# f7_General.net
KiCad netlist of a schematic drawn in EAGLE
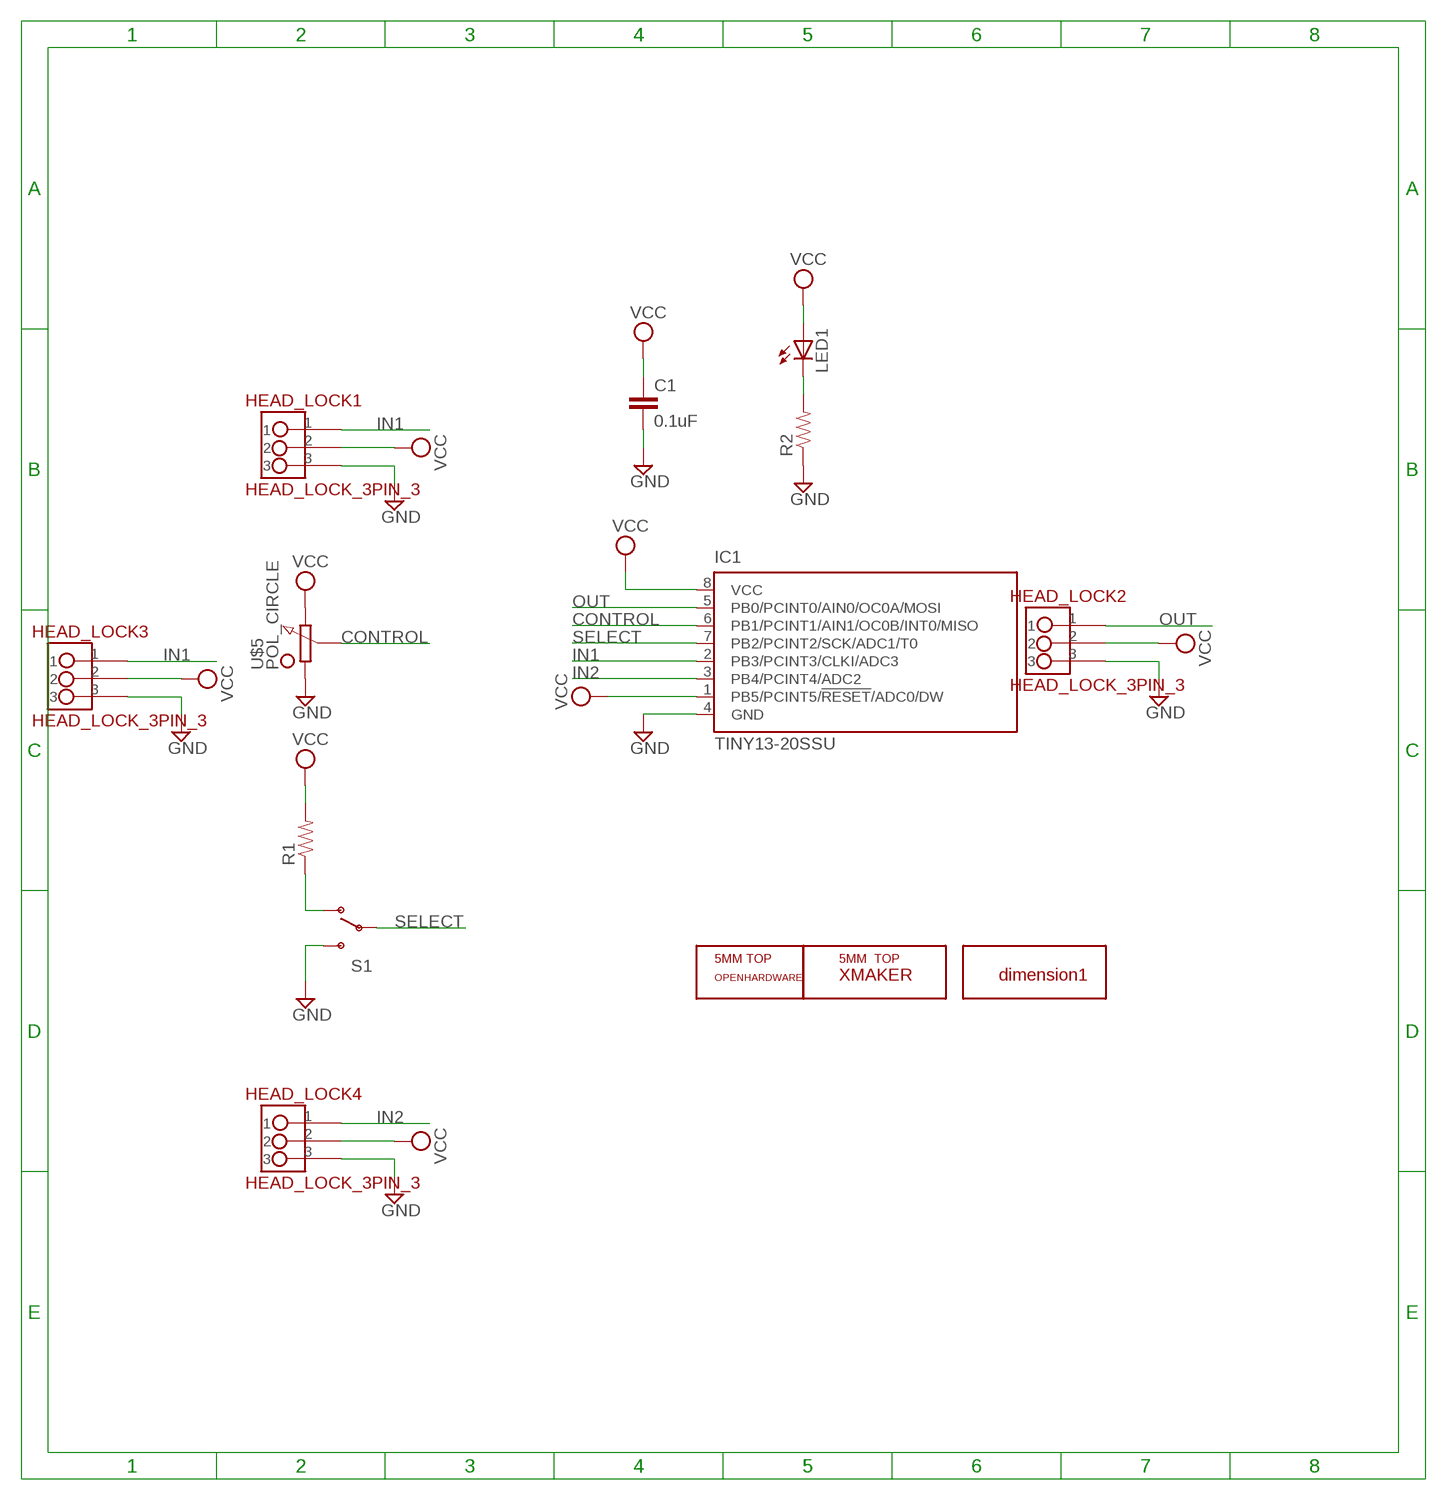
[diagram p0: schematic, sheet 1]

(export (version "E")
  (design (tool "Eeschema 10.0.6"))
  (components
    (comp (ref "C1")
      (value "0.1uF")
      (footprint "eagle-import:0603-CAP")
      (libsource (lib "eagle-import") (part "CAP0603-CAP"))
    )
    (comp (ref "HEAD_LOCK1")
      (value "HEAD_LOCK_3PIN_3")
      (footprint "eagle-import:HEAD_LOCK_3PIN_3")
      (libsource (lib "eagle-import") (part "HEAD_LOCK_3PIN_3"))
    )
    (comp (ref "HEAD_LOCK2")
      (value "HEAD_LOCK_3PIN_3")
      (footprint "eagle-import:HEAD_LOCK_3PIN_3")
      (libsource (lib "eagle-import") (part "HEAD_LOCK_3PIN_3"))
    )
    (comp (ref "HEAD_LOCK3")
      (value "HEAD_LOCK_3PIN_3")
      (footprint "eagle-import:HEAD_LOCK_3PIN_3")
      (libsource (lib "eagle-import") (part "HEAD_LOCK_3PIN_3"))
    )
    (comp (ref "HEAD_LOCK4")
      (value "HEAD_LOCK_3PIN_3")
      (footprint "eagle-import:HEAD_LOCK_3PIN_3")
      (libsource (lib "eagle-import") (part "HEAD_LOCK_3PIN_3"))
    )
    (comp (ref "IC1")
      (value "TINY13-20SSU")
      (footprint "eagle-import:8S1")
      (fields (field (name "MPN") "ATTINY13-20SSU"))
      (libsource (lib "eagle-import") (part "TINY13SSU-20"))
    )
    (comp (ref "LED1")
      (value "LED_ESML0603")
      (footprint "eagle-import:LED_SML0603")
      (libsource (lib "eagle-import") (part "LED_ESML0603"))
    )
    (comp (ref "R1")
      (value "RESISTOR0603-RES")
      (footprint "eagle-import:0603-RES")
      (libsource (lib "eagle-import") (part "RESISTOR0603-RES"))
    )
    (comp (ref "R2")
      (value "0.27OHM-1/10W-1%(0603)")
      (footprint "eagle-import:0603-RES")
      (libsource (lib "eagle-import") (part "0.27OHM-1/10W-1%(0603)"))
    )
    (comp (ref "S1")
      (value "SWITCH-SPDTKIT")
      (footprint "eagle-import:SWITCH-SPDT_KIT")
      (libsource (lib "eagle-import") (part "SWITCH-SPDTKIT"))
    )
    (comp (ref "U$2")
      (value "XMAKERLOGO_5MM_TOP")
      (footprint "eagle-import:XMAKERLOGO_5MM_TOP")
      (libsource (lib "eagle-import") (part "XMAKERLOGO_5MM_TOP"))
    )
    (comp (ref "U$3")
      (value "DIMENSION1")
      (footprint "eagle-import:DIMENSION1")
      (libsource (lib "eagle-import") (part "DIMENSION1"))
    )
    (comp (ref "U$4")
      (value "OPENHARDWARE_5MM_TOP")
      (footprint "eagle-import:OPENSOURCE_5MM_TOP")
      (libsource (lib "eagle-import") (part "OPENHARDWARE_5MM_TOP"))
    )
    (comp (ref "U$5")
      (value "POL_CIRCLE")
      (footprint "eagle-import:POT_CIRCLE")
      (libsource (lib "eagle-import") (part "POL_CIRCLE"))
    )
  )
  (nets
    (net (code "1") (name "/CONTROL") (class "Default")
      (node (ref "IC1") (pin "6") (pinfunction "PB1/PCINT1/AIN1/OC0B/INT0/MISO_6") (pintype "bidirectional"))
      (node (ref "U$5") (pin "P$2") (pinfunction "2_P$2") (pintype "passive"))
    )
    (net (code "2") (name "/IN1") (class "Default")
      (node (ref "HEAD_LOCK1") (pin "1") (pinfunction "1_1") (pintype "passive"))
      (node (ref "HEAD_LOCK3") (pin "1") (pinfunction "1_1") (pintype "passive"))
      (node (ref "IC1") (pin "2") (pinfunction "PB3/PCINT3/CLKI/ADC3_2") (pintype "bidirectional"))
    )
    (net (code "3") (name "/IN2") (class "Default")
      (node (ref "HEAD_LOCK4") (pin "1") (pinfunction "1_1") (pintype "passive"))
      (node (ref "IC1") (pin "3") (pinfunction "PB4/PCINT4/ADC2_3") (pintype "bidirectional"))
    )
    (net (code "4") (name "/OUT") (class "Default")
      (node (ref "HEAD_LOCK2") (pin "1") (pinfunction "1_1") (pintype "passive"))
      (node (ref "IC1") (pin "5") (pinfunction "PB0/PCINT0/AIN0/OC0A/MOSI_5") (pintype "bidirectional"))
    )
    (net (code "5") (name "/SELECT") (class "Default")
      (node (ref "IC1") (pin "7") (pinfunction "PB2/PCINT2/SCK/ADC1/T0_7") (pintype "bidirectional"))
      (node (ref "S1") (pin "2") (pinfunction "P_2") (pintype "passive"))
    )
    (net (code "6") (name "GND") (class "Default")
      (node (ref "C1") (pin "2") (pinfunction "2_2") (pintype "passive"))
      (node (ref "HEAD_LOCK1") (pin "3") (pinfunction "3_3") (pintype "passive"))
      (node (ref "HEAD_LOCK2") (pin "3") (pinfunction "3_3") (pintype "passive"))
      (node (ref "HEAD_LOCK3") (pin "3") (pinfunction "3_3") (pintype "passive"))
      (node (ref "HEAD_LOCK4") (pin "3") (pinfunction "3_3") (pintype "passive"))
      (node (ref "IC1") (pin "4") (pinfunction "GND_4") (pintype "power_in"))
      (node (ref "R2") (pin "1") (pinfunction "1_1") (pintype "passive"))
      (node (ref "S1") (pin "3") (pinfunction "S_3") (pintype "passive"))
      (node (ref "U$5") (pin "P$3") (pinfunction "3_P$3") (pintype "passive"))
    )
    (net (code "7") (name "Net-(LED1-PadC)") (class "Default")
      (node (ref "LED1") (pin "C") (pinfunction "C_C") (pintype "passive"))
      (node (ref "R2") (pin "2") (pinfunction "2_2") (pintype "passive"))
    )
    (net (code "8") (name "Net-(S1-O)") (class "Default")
      (node (ref "R1") (pin "1") (pinfunction "1_1") (pintype "passive"))
      (node (ref "S1") (pin "1") (pinfunction "O_1") (pintype "passive"))
    )
    (net (code "9") (name "VCC") (class "Default")
      (node (ref "C1") (pin "1") (pinfunction "1_1") (pintype "passive"))
      (node (ref "HEAD_LOCK1") (pin "2") (pinfunction "2_2") (pintype "passive"))
      (node (ref "HEAD_LOCK2") (pin "2") (pinfunction "2_2") (pintype "passive"))
      (node (ref "HEAD_LOCK3") (pin "2") (pinfunction "2_2") (pintype "passive"))
      (node (ref "HEAD_LOCK4") (pin "2") (pinfunction "2_2") (pintype "passive"))
      (node (ref "IC1") (pin "1") (pinfunction "PB5/PCINT5/~{RESET}/ADC0/DW_1") (pintype "bidirectional"))
      (node (ref "IC1") (pin "8") (pinfunction "VCC_8") (pintype "power_in"))
      (node (ref "LED1") (pin "A") (pinfunction "A_A") (pintype "passive"))
      (node (ref "R1") (pin "2") (pinfunction "2_2") (pintype "passive"))
      (node (ref "U$5") (pin "P$1") (pinfunction "1_P$1") (pintype "passive"))
    )
  )
)
